# qcopter_rfm_bb.net
KiCad netlist of a schematic drawn in EAGLE
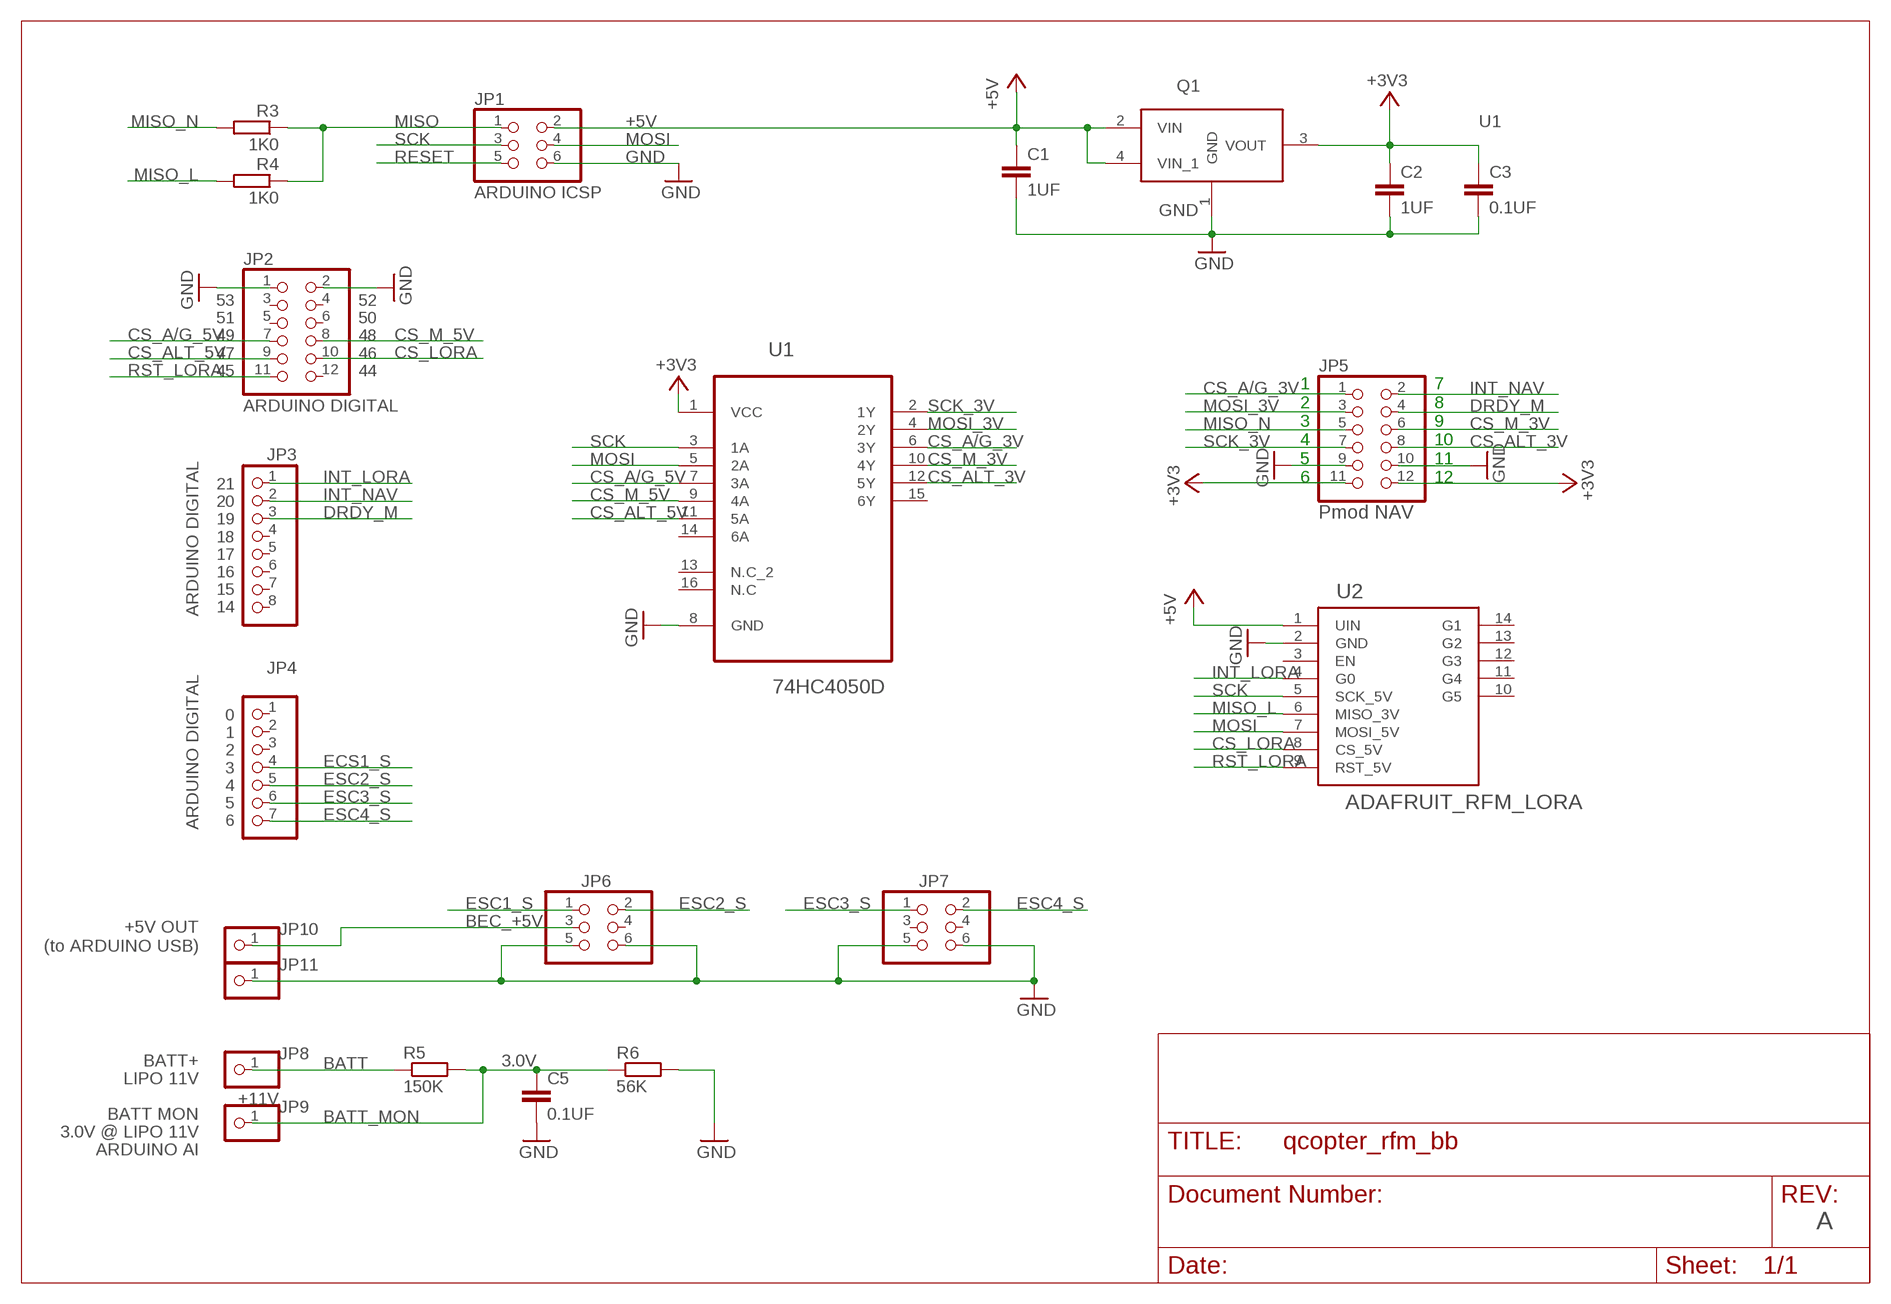
[diagram p0: schematic, sheet 1]

(export (version "E")
  (design (tool "Eeschema 10.0.6"))
  (components
    (comp (ref "C1")
      (value "1UF")
      (footprint "eagle-import:C1206")
      (libsource (lib "eagle-import") (part "C-EUC1206"))
    )
    (comp (ref "C2")
      (value "1UF")
      (footprint "eagle-import:C1206")
      (libsource (lib "eagle-import") (part "C-EUC1206"))
    )
    (comp (ref "C3")
      (value "0.1UF")
      (footprint "eagle-import:C1206")
      (libsource (lib "eagle-import") (part "C-EUC1206"))
    )
    (comp (ref "C5")
      (value "0.1UF")
      (footprint "eagle-import:C1206")
      (libsource (lib "eagle-import") (part "C-EUC1206"))
    )
    (comp (ref "JP1")
      (value "ARDUINO ICSP")
      (footprint "eagle-import:2X03")
      (libsource (lib "eagle-import") (part "PINHD-2X3"))
    )
    (comp (ref "JP2")
      (value "ARDUINO DIGITAL")
      (footprint "eagle-import:2X06")
      (libsource (lib "eagle-import") (part "PINHD-2X6"))
    )
    (comp (ref "JP3")
      (value "ARDUINO DIGITAL")
      (footprint "eagle-import:1X08")
      (libsource (lib "eagle-import") (part "PINHD-1X8"))
    )
    (comp (ref "JP4")
      (value "ARDUINO DIGITAL")
      (footprint "eagle-import:1X07")
      (libsource (lib "eagle-import") (part "PINHD-1X7"))
    )
    (comp (ref "JP5")
      (value "Pmod NAV")
      (footprint "eagle-import:2X06_90")
      (libsource (lib "eagle-import") (part "PINHD-2X6/90"))
    )
    (comp (ref "JP6")
      (value "PINHD-2X3")
      (footprint "eagle-import:2X03")
      (libsource (lib "eagle-import") (part "PINHD-2X3"))
    )
    (comp (ref "JP7")
      (value "PINHD-2X3")
      (footprint "eagle-import:2X03")
      (libsource (lib "eagle-import") (part "PINHD-2X3"))
    )
    (comp (ref "JP8")
      (value "+11V")
      (footprint "eagle-import:1X01")
      (libsource (lib "eagle-import") (part "PINHD-1X1"))
    )
    (comp (ref "JP9")
      (value "PINHD-1X1")
      (footprint "eagle-import:1X01")
      (libsource (lib "eagle-import") (part "PINHD-1X1"))
    )
    (comp (ref "JP10")
      (value "PINHD-1X1")
      (footprint "eagle-import:1X01")
      (libsource (lib "eagle-import") (part "PINHD-1X1"))
    )
    (comp (ref "JP11")
      (value "PINHD-1X1")
      (footprint "eagle-import:1X01")
      (libsource (lib "eagle-import") (part "PINHD-1X1"))
    )
    (comp (ref "Q1")
      (value "MCP17-MCP1703T-3302E/MB")
      (footprint "eagle-import:SOT150P400X160-4N")
      (fields (field (name "MPN") "MCP1703T-3302E/MB "))
      (libsource (lib "eagle-import") (part "MCP17-MCP1703T-3302E/MB"))
    )
    (comp (ref "R3")
      (value "1K0")
      (footprint "eagle-import:R1206")
      (libsource (lib "eagle-import") (part "R-EU_R1206"))
    )
    (comp (ref "R4")
      (value "1K0")
      (footprint "eagle-import:R1206")
      (libsource (lib "eagle-import") (part "R-EU_R1206"))
    )
    (comp (ref "R5")
      (value "150K")
      (footprint "eagle-import:R1206")
      (libsource (lib "eagle-import") (part "R-EU_R1206"))
    )
    (comp (ref "R6")
      (value "56K")
      (footprint "eagle-import:R1206")
      (libsource (lib "eagle-import") (part "R-EU_R1206"))
    )
    (comp (ref "U1")
      (value "74HC4050D")
      (footprint "eagle-import:SOIC127P600X175-16N")
      (libsource (lib "eagle-import") (part "74HC4050D"))
    )
    (comp (ref "U2")
      (value "ADAFRUIT_RFM_LORA")
      (footprint "eagle-import:ADAFRUIT_RFM_LORA_B")
      (libsource (lib "eagle-import") (part "ADAFRUIT_RFM_LORA"))
    )
  )
  (nets
    (net (code "1") (name "+3V3") (class "Default")
      (node (ref "C2") (pin "1") (pinfunction "1_1") (pintype "passive"))
      (node (ref "C3") (pin "1") (pinfunction "1_1") (pintype "passive"))
      (node (ref "JP5") (pin "11") (pinfunction "11_11") (pintype "passive"))
      (node (ref "JP5") (pin "12") (pinfunction "12_12") (pintype "passive"))
      (node (ref "Q1") (pin "3") (pinfunction "VOUT_3") (pintype "output"))
      (node (ref "U1") (pin "1") (pinfunction "VCC_1") (pintype "power_in"))
    )
    (net (code "2") (name "+5V") (class "Default")
      (node (ref "C1") (pin "1") (pinfunction "1_1") (pintype "passive"))
      (node (ref "JP1") (pin "2") (pinfunction "2_2") (pintype "passive"))
      (node (ref "Q1") (pin "2") (pinfunction "VIN_2") (pintype "input"))
      (node (ref "Q1") (pin "4") (pinfunction "VIN_1_4") (pintype "input"))
      (node (ref "U2") (pin "1") (pinfunction "UIN_1") (pintype "power_in"))
    )
    (net (code "3") (name "/BATT") (class "Default")
      (node (ref "JP8") (pin "1") (pinfunction "1_1") (pintype "passive"))
      (node (ref "R5") (pin "1") (pinfunction "1_1") (pintype "passive"))
    )
    (net (code "4") (name "/BATT_MON") (class "Default")
      (node (ref "C5") (pin "1") (pinfunction "1_1") (pintype "passive"))
      (node (ref "JP9") (pin "1") (pinfunction "1_1") (pintype "passive"))
      (node (ref "R5") (pin "2") (pinfunction "2_2") (pintype "passive"))
      (node (ref "R6") (pin "1") (pinfunction "1_1") (pintype "passive"))
    )
    (net (code "5") (name "/BEC_+5V") (class "Default")
      (node (ref "JP10") (pin "1") (pinfunction "1_1") (pintype "passive"))
      (node (ref "JP6") (pin "3") (pinfunction "3_3") (pintype "passive"))
    )
    (net (code "6") (name "/CS_ALT_3V") (class "Default")
      (node (ref "JP5") (pin "8") (pinfunction "8_8") (pintype "passive"))
      (node (ref "U1") (pin "12") (pinfunction "5Y_12") (pintype "output"))
    )
    (net (code "7") (name "/CS_ALT_5V") (class "Default")
      (node (ref "JP2") (pin "9") (pinfunction "9_9") (pintype "passive"))
      (node (ref "U1") (pin "11") (pinfunction "5A_11") (pintype "input"))
    )
    (net (code "8") (name "/CS_A{slash}G_3V") (class "Default")
      (node (ref "JP5") (pin "1") (pinfunction "1_1") (pintype "passive"))
      (node (ref "U1") (pin "6") (pinfunction "3Y_6") (pintype "output"))
    )
    (net (code "9") (name "/CS_A{slash}G_5V") (class "Default")
      (node (ref "JP2") (pin "7") (pinfunction "7_7") (pintype "passive"))
      (node (ref "U1") (pin "7") (pinfunction "3A_7") (pintype "input"))
    )
    (net (code "10") (name "/CS_LORA") (class "Default")
      (node (ref "JP2") (pin "10") (pinfunction "10_10") (pintype "passive"))
      (node (ref "U2") (pin "8") (pinfunction "CS_5V_8") (pintype "input"))
    )
    (net (code "11") (name "/CS_M_3V") (class "Default")
      (node (ref "JP5") (pin "6") (pinfunction "6_6") (pintype "passive"))
      (node (ref "U1") (pin "10") (pinfunction "4Y_10") (pintype "output"))
    )
    (net (code "12") (name "/CS_M_5V") (class "Default")
      (node (ref "JP2") (pin "8") (pinfunction "8_8") (pintype "passive"))
      (node (ref "U1") (pin "9") (pinfunction "4A_9") (pintype "input"))
    )
    (net (code "13") (name "/DRDY_M") (class "Default")
      (node (ref "JP3") (pin "3") (pinfunction "3_3") (pintype "passive"))
      (node (ref "JP5") (pin "4") (pinfunction "4_4") (pintype "passive"))
    )
    (net (code "14") (name "/ECS1_S") (class "Default")
      (node (ref "JP4") (pin "4") (pinfunction "4_4") (pintype "passive"))
    )
    (net (code "15") (name "/ESC1_S") (class "Default")
      (node (ref "JP6") (pin "1") (pinfunction "1_1") (pintype "passive"))
    )
    (net (code "16") (name "/ESC2_S") (class "Default")
      (node (ref "JP4") (pin "5") (pinfunction "5_5") (pintype "passive"))
      (node (ref "JP6") (pin "2") (pinfunction "2_2") (pintype "passive"))
    )
    (net (code "17") (name "/ESC3_S") (class "Default")
      (node (ref "JP4") (pin "6") (pinfunction "6_6") (pintype "passive"))
      (node (ref "JP7") (pin "1") (pinfunction "1_1") (pintype "passive"))
    )
    (net (code "18") (name "/ESC4_S") (class "Default")
      (node (ref "JP4") (pin "7") (pinfunction "7_7") (pintype "passive"))
      (node (ref "JP7") (pin "2") (pinfunction "2_2") (pintype "passive"))
    )
    (net (code "19") (name "/INT_LORA") (class "Default")
      (node (ref "JP3") (pin "1") (pinfunction "1_1") (pintype "passive"))
      (node (ref "U2") (pin "4") (pinfunction "G0_4") (pintype "output"))
    )
    (net (code "20") (name "/INT_NAV") (class "Default")
      (node (ref "JP3") (pin "2") (pinfunction "2_2") (pintype "passive"))
      (node (ref "JP5") (pin "2") (pinfunction "2_2") (pintype "passive"))
    )
    (net (code "21") (name "/MISO") (class "Default")
      (node (ref "JP1") (pin "1") (pinfunction "1_1") (pintype "passive"))
      (node (ref "R3") (pin "1") (pinfunction "1_1") (pintype "passive"))
      (node (ref "R4") (pin "1") (pinfunction "1_1") (pintype "passive"))
    )
    (net (code "22") (name "/MISO_L") (class "Default")
      (node (ref "R4") (pin "2") (pinfunction "2_2") (pintype "passive"))
      (node (ref "U2") (pin "6") (pinfunction "MISO_3V_6") (pintype "output"))
    )
    (net (code "23") (name "/MISO_N") (class "Default")
      (node (ref "JP5") (pin "5") (pinfunction "5_5") (pintype "passive"))
      (node (ref "R3") (pin "2") (pinfunction "2_2") (pintype "passive"))
    )
    (net (code "24") (name "/MOSI") (class "Default")
      (node (ref "JP1") (pin "4") (pinfunction "4_4") (pintype "passive"))
      (node (ref "U1") (pin "5") (pinfunction "2A_5") (pintype "input"))
      (node (ref "U2") (pin "7") (pinfunction "MOSI_5V_7") (pintype "input"))
    )
    (net (code "25") (name "/MOSI_3V") (class "Default")
      (node (ref "JP5") (pin "3") (pinfunction "3_3") (pintype "passive"))
      (node (ref "U1") (pin "4") (pinfunction "2Y_4") (pintype "output"))
    )
    (net (code "26") (name "/RESET") (class "Default")
      (node (ref "JP1") (pin "5") (pinfunction "5_5") (pintype "passive"))
    )
    (net (code "27") (name "/RST_LORA") (class "Default")
      (node (ref "JP2") (pin "11") (pinfunction "11_11") (pintype "passive"))
      (node (ref "U2") (pin "9") (pinfunction "RST_5V_9") (pintype "input"))
    )
    (net (code "28") (name "/SCK") (class "Default")
      (node (ref "JP1") (pin "3") (pinfunction "3_3") (pintype "passive"))
      (node (ref "U1") (pin "3") (pinfunction "1A_3") (pintype "input"))
      (node (ref "U2") (pin "5") (pinfunction "SCK_5V_5") (pintype "input"))
    )
    (net (code "29") (name "/SCK_3V") (class "Default")
      (node (ref "JP5") (pin "7") (pinfunction "7_7") (pintype "passive"))
      (node (ref "U1") (pin "2") (pinfunction "1Y_2") (pintype "output"))
    )
    (net (code "30") (name "GND") (class "Default")
      (node (ref "C1") (pin "2") (pinfunction "2_2") (pintype "passive"))
      (node (ref "C2") (pin "2") (pinfunction "2_2") (pintype "passive"))
      (node (ref "C3") (pin "2") (pinfunction "2_2") (pintype "passive"))
      (node (ref "C5") (pin "2") (pinfunction "2_2") (pintype "passive"))
      (node (ref "JP1") (pin "6") (pinfunction "6_6") (pintype "passive"))
      (node (ref "JP11") (pin "1") (pinfunction "1_1") (pintype "passive"))
      (node (ref "JP2") (pin "1") (pinfunction "1_1") (pintype "passive"))
      (node (ref "JP2") (pin "2") (pinfunction "2_2") (pintype "passive"))
      (node (ref "JP5") (pin "10") (pinfunction "10_10") (pintype "passive"))
      (node (ref "JP5") (pin "9") (pinfunction "9_9") (pintype "passive"))
      (node (ref "JP6") (pin "5") (pinfunction "5_5") (pintype "passive"))
      (node (ref "JP6") (pin "6") (pinfunction "6_6") (pintype "passive"))
      (node (ref "JP7") (pin "5") (pinfunction "5_5") (pintype "passive"))
      (node (ref "JP7") (pin "6") (pinfunction "6_6") (pintype "passive"))
      (node (ref "Q1") (pin "1") (pinfunction "GND_1") (pintype "power_in"))
      (node (ref "R6") (pin "2") (pinfunction "2_2") (pintype "passive"))
      (node (ref "U1") (pin "8") (pinfunction "GND_8") (pintype "passive"))
      (node (ref "U2") (pin "2") (pinfunction "GND_2") (pintype "power_in"))
    )
    (net (code "31") (name "unconnected-(JP2-Pad3)") (class "Default")
      (node (ref "JP2") (pin "3") (pinfunction "3_3") (pintype "passive"))
    )
    (net (code "32") (name "unconnected-(JP2-Pad4)") (class "Default")
      (node (ref "JP2") (pin "4") (pinfunction "4_4") (pintype "passive"))
    )
    (net (code "33") (name "unconnected-(JP2-Pad5)") (class "Default")
      (node (ref "JP2") (pin "5") (pinfunction "5_5") (pintype "passive"))
    )
    (net (code "34") (name "unconnected-(JP2-Pad6)") (class "Default")
      (node (ref "JP2") (pin "6") (pinfunction "6_6") (pintype "passive"))
    )
    (net (code "35") (name "unconnected-(JP2-Pad12)") (class "Default")
      (node (ref "JP2") (pin "12") (pinfunction "12_12") (pintype "passive"))
    )
    (net (code "36") (name "unconnected-(JP3-Pad4)") (class "Default")
      (node (ref "JP3") (pin "4") (pinfunction "4_4") (pintype "passive"))
    )
    (net (code "37") (name "unconnected-(JP3-Pad5)") (class "Default")
      (node (ref "JP3") (pin "5") (pinfunction "5_5") (pintype "passive"))
    )
    (net (code "38") (name "unconnected-(JP3-Pad6)") (class "Default")
      (node (ref "JP3") (pin "6") (pinfunction "6_6") (pintype "passive"))
    )
    (net (code "39") (name "unconnected-(JP3-Pad7)") (class "Default")
      (node (ref "JP3") (pin "7") (pinfunction "7_7") (pintype "passive"))
    )
    (net (code "40") (name "unconnected-(JP3-Pad8)") (class "Default")
      (node (ref "JP3") (pin "8") (pinfunction "8_8") (pintype "passive"))
    )
    (net (code "41") (name "unconnected-(JP4-Pad1)") (class "Default")
      (node (ref "JP4") (pin "1") (pinfunction "1_1") (pintype "passive"))
    )
    (net (code "42") (name "unconnected-(JP4-Pad2)") (class "Default")
      (node (ref "JP4") (pin "2") (pinfunction "2_2") (pintype "passive"))
    )
    (net (code "43") (name "unconnected-(JP4-Pad3)") (class "Default")
      (node (ref "JP4") (pin "3") (pinfunction "3_3") (pintype "passive"))
    )
    (net (code "44") (name "unconnected-(JP6-Pad4)") (class "Default")
      (node (ref "JP6") (pin "4") (pinfunction "4_4") (pintype "passive"))
    )
    (net (code "45") (name "unconnected-(JP7-Pad3)") (class "Default")
      (node (ref "JP7") (pin "3") (pinfunction "3_3") (pintype "passive"))
    )
    (net (code "46") (name "unconnected-(JP7-Pad4)") (class "Default")
      (node (ref "JP7") (pin "4") (pinfunction "4_4") (pintype "passive"))
    )
    (net (code "47") (name "unconnected-(U1-6A-Pad14)") (class "Default")
      (node (ref "U1") (pin "14") (pinfunction "6A_14") (pintype "input"))
    )
    (net (code "48") (name "unconnected-(U1-6Y-Pad15)") (class "Default")
      (node (ref "U1") (pin "15") (pinfunction "6Y_15") (pintype "output"))
    )
    (net (code "49") (name "unconnected-(U1-N.C-Pad16)") (class "Default")
      (node (ref "U1") (pin "16") (pinfunction "N.C_16") (pintype "no_connect"))
    )
    (net (code "50") (name "unconnected-(U1-N.C_2-Pad13)") (class "Default")
      (node (ref "U1") (pin "13") (pinfunction "N.C_2_13") (pintype "no_connect"))
    )
    (net (code "51") (name "unconnected-(U2-EN-Pad3)") (class "Default")
      (node (ref "U2") (pin "3") (pinfunction "EN_3") (pintype "input"))
    )
    (net (code "52") (name "unconnected-(U2-G1-Pad14)") (class "Default")
      (node (ref "U2") (pin "14") (pinfunction "G1_14") (pintype "bidirectional"))
    )
    (net (code "53") (name "unconnected-(U2-G2-Pad13)") (class "Default")
      (node (ref "U2") (pin "13") (pinfunction "G2_13") (pintype "bidirectional"))
    )
    (net (code "54") (name "unconnected-(U2-G3-Pad12)") (class "Default")
      (node (ref "U2") (pin "12") (pinfunction "G3_12") (pintype "bidirectional"))
    )
    (net (code "55") (name "unconnected-(U2-G4-Pad11)") (class "Default")
      (node (ref "U2") (pin "11") (pinfunction "G4_11") (pintype "bidirectional"))
    )
    (net (code "56") (name "unconnected-(U2-G5-Pad10)") (class "Default")
      (node (ref "U2") (pin "10") (pinfunction "G5_10") (pintype "bidirectional"))
    )
  )
)
